# ice_tube_clock.net
KiCad netlist of a schematic drawn in EAGLE
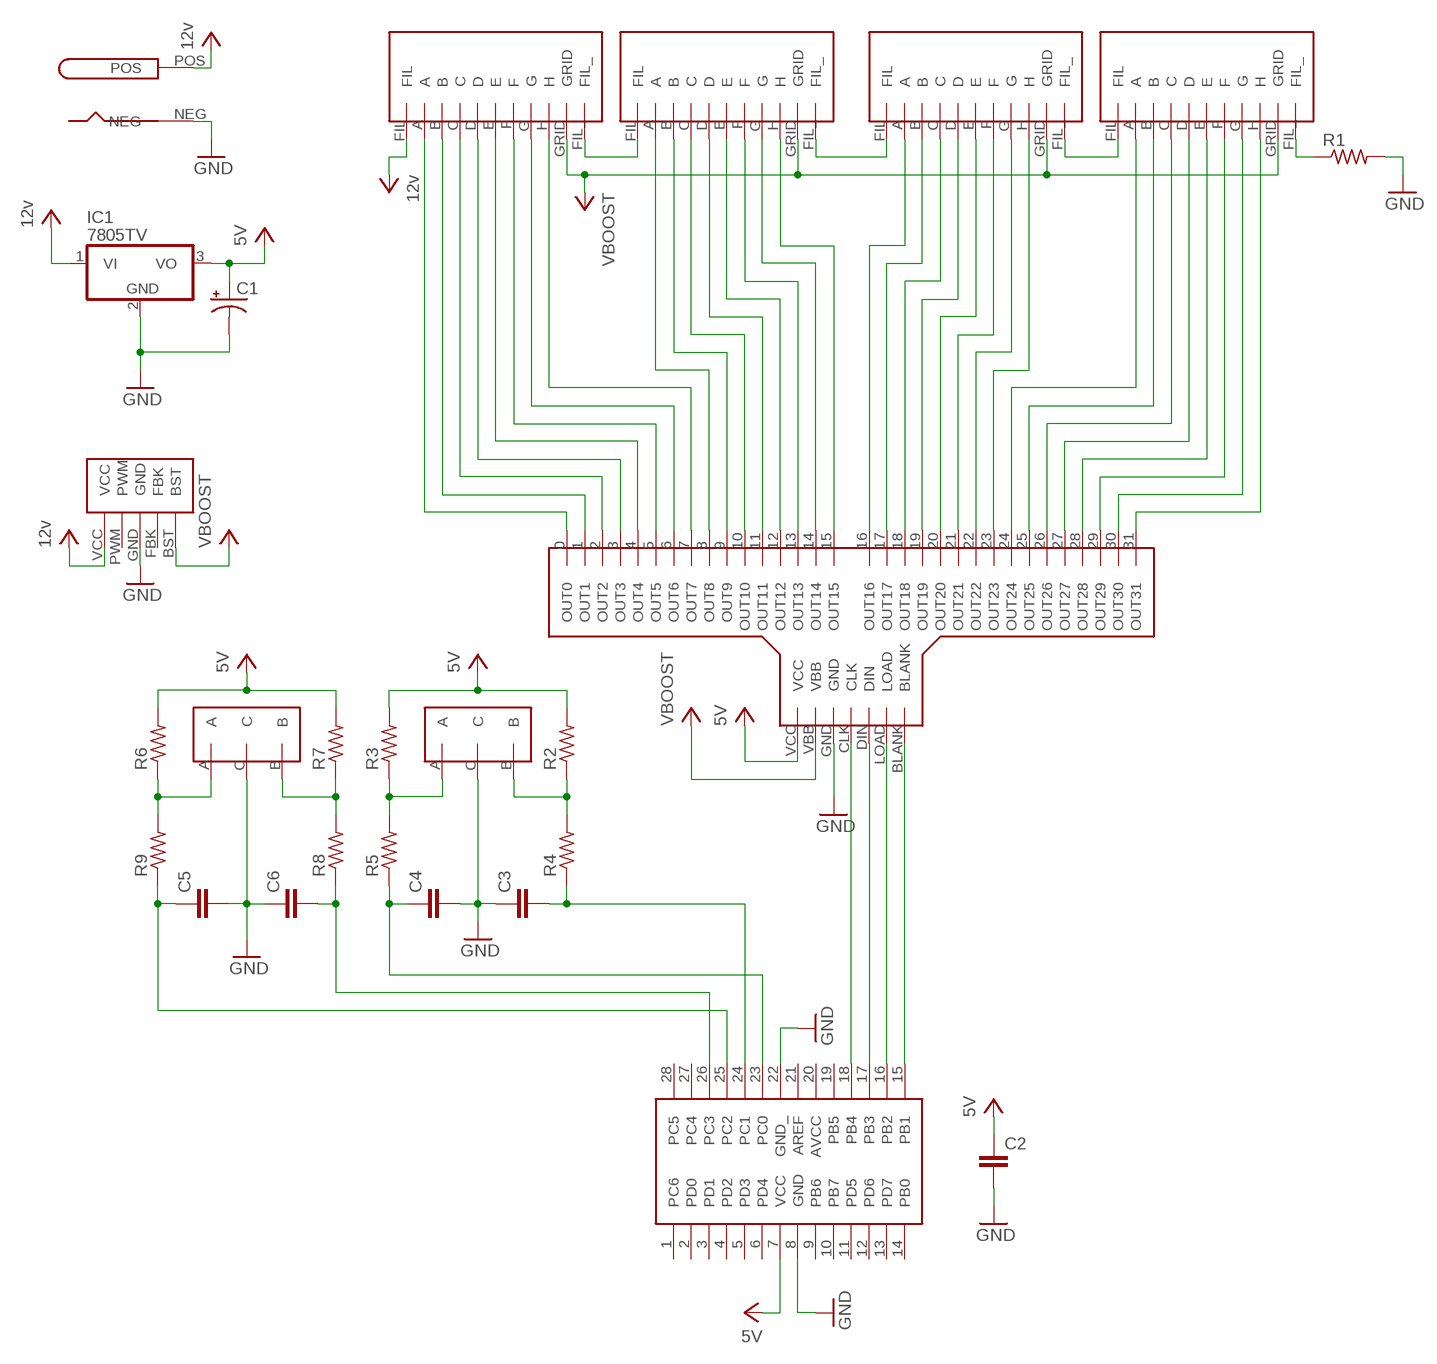
[diagram p0: schematic, sheet 1]

(export (version "E")
  (design (tool "Eeschema 10.0.6"))
  (components
    (comp (ref "C1")
      (value "CAP_POLPTH1")
      (footprint "eagle-import:CPOL-RADIAL-100UF-25V")
      (libsource (lib "eagle-import") (part "CAP_POLPTH1"))
    )
    (comp (ref "C2")
      (value "0.1UF-50V-20%(PTH)KIT-EZ")
      (footprint "eagle-import:CAP-PTH-SMALL-KIT")
      (libsource (lib "eagle-import") (part "0.1UF-50V-20%(PTH)KIT-EZ"))
    )
    (comp (ref "C3")
      (value "0.1UF-50V-20%(PTH)KIT-EZ")
      (footprint "eagle-import:CAP-PTH-SMALL-KIT")
      (libsource (lib "eagle-import") (part "0.1UF-50V-20%(PTH)KIT-EZ"))
    )
    (comp (ref "C4")
      (value "0.1UF-50V-20%(PTH)KIT-EZ")
      (footprint "eagle-import:CAP-PTH-SMALL-KIT")
      (libsource (lib "eagle-import") (part "0.1UF-50V-20%(PTH)KIT-EZ"))
    )
    (comp (ref "C5")
      (value "0.1UF-50V-20%(PTH)KIT-EZ")
      (footprint "eagle-import:CAP-PTH-SMALL-KIT")
      (libsource (lib "eagle-import") (part "0.1UF-50V-20%(PTH)KIT-EZ"))
    )
    (comp (ref "C6")
      (value "0.1UF-50V-20%(PTH)KIT-EZ")
      (footprint "eagle-import:CAP-PTH-SMALL-KIT")
      (libsource (lib "eagle-import") (part "0.1UF-50V-20%(PTH)KIT-EZ"))
    )
    (comp (ref "IC1")
      (value "7805TV")
      (footprint "eagle-import:TO220V")
      (libsource (lib "eagle-import") (part "78TV05"))
    )
    (comp (ref "R1")
      (value "R-US_0204/7")
      (footprint "eagle-import:0204_7")
      (libsource (lib "eagle-import") (part "R-US_0204/7"))
    )
    (comp (ref "R2")
      (value "R-US_0204/7")
      (footprint "eagle-import:0204_7")
      (libsource (lib "eagle-import") (part "R-US_0204/7"))
    )
    (comp (ref "R3")
      (value "R-US_0204/7")
      (footprint "eagle-import:0204_7")
      (libsource (lib "eagle-import") (part "R-US_0204/7"))
    )
    (comp (ref "R4")
      (value "R-US_0204/7")
      (footprint "eagle-import:0204_7")
      (libsource (lib "eagle-import") (part "R-US_0204/7"))
    )
    (comp (ref "R5")
      (value "R-US_0204/7")
      (footprint "eagle-import:0204_7")
      (libsource (lib "eagle-import") (part "R-US_0204/7"))
    )
    (comp (ref "R6")
      (value "R-US_0204/7")
      (footprint "eagle-import:0204_7")
      (libsource (lib "eagle-import") (part "R-US_0204/7"))
    )
    (comp (ref "R7")
      (value "R-US_0204/7")
      (footprint "eagle-import:0204_7")
      (libsource (lib "eagle-import") (part "R-US_0204/7"))
    )
    (comp (ref "R8")
      (value "R-US_0204/7")
      (footprint "eagle-import:0204_7")
      (libsource (lib "eagle-import") (part "R-US_0204/7"))
    )
    (comp (ref "R9")
      (value "R-US_0204/7")
      (footprint "eagle-import:0204_7")
      (libsource (lib "eagle-import") (part "R-US_0204/7"))
    )
    (comp (ref "U$1")
      (value "ATMEGA168-DIP28")
      (footprint "eagle-import:DIP28")
      (libsource (lib "eagle-import") (part "ATMEGA168-DIP28"))
    )
    (comp (ref "U$2")
      (value "IV11-BOOST-SUPPLY")
      (footprint "eagle-import:IV11-BOOST-SUPPLY")
      (libsource (lib "eagle-import") (part "IV11-BOOST-SUPPLY"))
    )
    (comp (ref "U$3")
      (value "IV-11-CARRIER")
      (footprint "eagle-import:IV-11-CARRIER")
      (libsource (lib "eagle-import") (part "IV-11-CARRIER"))
    )
    (comp (ref "U$4")
      (value "IV-11-CARRIER")
      (footprint "eagle-import:IV-11-CARRIER")
      (libsource (lib "eagle-import") (part "IV-11-CARRIER"))
    )
    (comp (ref "U$5")
      (value "IV-11-CARRIER")
      (footprint "eagle-import:IV-11-CARRIER")
      (libsource (lib "eagle-import") (part "IV-11-CARRIER"))
    )
    (comp (ref "U$6")
      (value "IV-11-CARRIER")
      (footprint "eagle-import:IV-11-CARRIER")
      (libsource (lib "eagle-import") (part "IV-11-CARRIER"))
    )
    (comp (ref "U$7")
      (value "PJ-037A")
      (footprint "eagle-import:PJ-037A")
      (libsource (lib "eagle-import") (part "PJ-037A"))
    )
    (comp (ref "U$8")
      (value "VFD-DRIVER-CARRIER")
      (footprint "eagle-import:VFD-DRIVER-CARRIER")
      (libsource (lib "eagle-import") (part "VFD-DRIVER-CARRIER"))
    )
    (comp (ref "U$9")
      (value "PEL12S")
      (footprint "eagle-import:PEL12S")
      (libsource (lib "eagle-import") (part "PEL12S"))
    )
    (comp (ref "U$10")
      (value "PEL12S")
      (footprint "eagle-import:PEL12S")
      (libsource (lib "eagle-import") (part "PEL12S"))
    )
  )
  (nets
    (net (code "1") (name "5V") (class "Default")
      (node (ref "C1") (pin "1") (pinfunction "+_1") (pintype "passive"))
      (node (ref "C2") (pin "1") (pinfunction "1_1") (pintype "passive"))
      (node (ref "IC1") (pin "3") (pinfunction "VO_3") (pintype "passive"))
      (node (ref "R2") (pin "2") (pinfunction "2_2") (pintype "passive"))
      (node (ref "R3") (pin "2") (pinfunction "2_2") (pintype "passive"))
      (node (ref "R6") (pin "2") (pinfunction "2_2") (pintype "passive"))
      (node (ref "R7") (pin "2") (pinfunction "2_2") (pintype "passive"))
      (node (ref "U$1") (pin "7") (pinfunction "VCC_7") (pintype "bidirectional"))
      (node (ref "U$8") (pin "VCC") (pinfunction "VCC_VCC") (pintype "bidirectional"))
    )
    (net (code "2") (name "12v") (class "Default")
      (node (ref "IC1") (pin "1") (pinfunction "VI_1") (pintype "input"))
      (node (ref "U$2") (pin "VCC") (pinfunction "VCC_VCC") (pintype "bidirectional"))
      (node (ref "U$3") (pin "FIL") (pinfunction "FIL_FIL") (pintype "bidirectional"))
      (node (ref "U$7") (pin "POS") (pinfunction "POS_POS") (pintype "bidirectional"))
    )
    (net (code "3") (name "GND") (class "Default")
      (node (ref "C1") (pin "2") (pinfunction "-_2") (pintype "passive"))
      (node (ref "C2") (pin "2") (pinfunction "2_2") (pintype "passive"))
      (node (ref "C3") (pin "1") (pinfunction "1_1") (pintype "passive"))
      (node (ref "C4") (pin "2") (pinfunction "2_2") (pintype "passive"))
      (node (ref "C5") (pin "2") (pinfunction "2_2") (pintype "passive"))
      (node (ref "C6") (pin "1") (pinfunction "1_1") (pintype "passive"))
      (node (ref "IC1") (pin "2") (pinfunction "GND_2") (pintype "passive"))
      (node (ref "R1") (pin "2") (pinfunction "2_2") (pintype "passive"))
      (node (ref "U$1") (pin "22") (pinfunction "GND__22") (pintype "bidirectional"))
      (node (ref "U$1") (pin "8") (pinfunction "GND_8") (pintype "bidirectional"))
      (node (ref "U$10") (pin "C") (pinfunction "C_C") (pintype "bidirectional"))
      (node (ref "U$2") (pin "GND") (pinfunction "GND_GND") (pintype "bidirectional"))
      (node (ref "U$7") (pin "NEG") (pinfunction "NEG_NEG") (pintype "bidirectional"))
      (node (ref "U$8") (pin "GND") (pinfunction "GND_GND") (pintype "bidirectional"))
      (node (ref "U$9") (pin "C") (pinfunction "C_C") (pintype "bidirectional"))
    )
    (net (code "4") (name "Net-(R1-Pad1)") (class "Default")
      (node (ref "R1") (pin "1") (pinfunction "1_1") (pintype "passive"))
      (node (ref "U$6") (pin "FIL_") (pinfunction "FIL__FIL_") (pintype "bidirectional"))
    )
    (net (code "5") (name "Net-(R2-Pad1)") (class "Default")
      (node (ref "R2") (pin "1") (pinfunction "1_1") (pintype "passive"))
      (node (ref "R4") (pin "2") (pinfunction "2_2") (pintype "passive"))
      (node (ref "U$10") (pin "B") (pinfunction "B_B") (pintype "bidirectional"))
    )
    (net (code "6") (name "Net-(R3-Pad1)") (class "Default")
      (node (ref "R3") (pin "1") (pinfunction "1_1") (pintype "passive"))
      (node (ref "R5") (pin "2") (pinfunction "2_2") (pintype "passive"))
      (node (ref "U$10") (pin "A") (pinfunction "A_A") (pintype "bidirectional"))
    )
    (net (code "7") (name "Net-(R6-Pad1)") (class "Default")
      (node (ref "R6") (pin "1") (pinfunction "1_1") (pintype "passive"))
      (node (ref "R9") (pin "2") (pinfunction "2_2") (pintype "passive"))
      (node (ref "U$9") (pin "A") (pinfunction "A_A") (pintype "bidirectional"))
    )
    (net (code "8") (name "Net-(R7-Pad1)") (class "Default")
      (node (ref "R7") (pin "1") (pinfunction "1_1") (pintype "passive"))
      (node (ref "R8") (pin "2") (pinfunction "2_2") (pintype "passive"))
      (node (ref "U$9") (pin "B") (pinfunction "B_B") (pintype "bidirectional"))
    )
    (net (code "9") (name "Net-(U$1-PB1)") (class "Default")
      (node (ref "U$1") (pin "15") (pinfunction "PB1_15") (pintype "bidirectional"))
      (node (ref "U$8") (pin "BLANK") (pinfunction "BLANK_BLANK") (pintype "bidirectional"))
    )
    (net (code "10") (name "Net-(U$1-PB2)") (class "Default")
      (node (ref "U$1") (pin "16") (pinfunction "PB2_16") (pintype "bidirectional"))
      (node (ref "U$8") (pin "LOAD") (pinfunction "LOAD_LOAD") (pintype "bidirectional"))
    )
    (net (code "11") (name "Net-(U$1-PB3)") (class "Default")
      (node (ref "U$1") (pin "17") (pinfunction "PB3_17") (pintype "bidirectional"))
      (node (ref "U$8") (pin "DIN") (pinfunction "DIN_DIN") (pintype "bidirectional"))
    )
    (net (code "12") (name "Net-(U$1-PB4)") (class "Default")
      (node (ref "U$1") (pin "18") (pinfunction "PB4_18") (pintype "bidirectional"))
      (node (ref "U$8") (pin "CLK") (pinfunction "CLK_CLK") (pintype "bidirectional"))
    )
    (net (code "13") (name "Net-(U$1-PC0)") (class "Default")
      (node (ref "C4") (pin "1") (pinfunction "1_1") (pintype "passive"))
      (node (ref "R5") (pin "1") (pinfunction "1_1") (pintype "passive"))
      (node (ref "U$1") (pin "23") (pinfunction "PC0_23") (pintype "bidirectional"))
    )
    (net (code "14") (name "Net-(U$1-PC1)") (class "Default")
      (node (ref "C3") (pin "2") (pinfunction "2_2") (pintype "passive"))
      (node (ref "R4") (pin "1") (pinfunction "1_1") (pintype "passive"))
      (node (ref "U$1") (pin "24") (pinfunction "PC1_24") (pintype "bidirectional"))
    )
    (net (code "15") (name "Net-(U$1-PC2)") (class "Default")
      (node (ref "C5") (pin "1") (pinfunction "1_1") (pintype "passive"))
      (node (ref "R9") (pin "1") (pinfunction "1_1") (pintype "passive"))
      (node (ref "U$1") (pin "25") (pinfunction "PC2_25") (pintype "bidirectional"))
    )
    (net (code "16") (name "Net-(U$1-PC3)") (class "Default")
      (node (ref "C6") (pin "2") (pinfunction "2_2") (pintype "passive"))
      (node (ref "R8") (pin "1") (pinfunction "1_1") (pintype "passive"))
      (node (ref "U$1") (pin "26") (pinfunction "PC3_26") (pintype "bidirectional"))
    )
    (net (code "17") (name "Net-(U$3-PadFIL_)") (class "Default")
      (node (ref "U$3") (pin "FIL_") (pinfunction "FIL__FIL_") (pintype "bidirectional"))
      (node (ref "U$4") (pin "FIL") (pinfunction "FIL_FIL") (pintype "bidirectional"))
    )
    (net (code "18") (name "Net-(U$4-PadFIL_)") (class "Default")
      (node (ref "U$4") (pin "FIL_") (pinfunction "FIL__FIL_") (pintype "bidirectional"))
      (node (ref "U$5") (pin "FIL") (pinfunction "FIL_FIL") (pintype "bidirectional"))
    )
    (net (code "19") (name "Net-(U$5-PadFIL_)") (class "Default")
      (node (ref "U$5") (pin "FIL_") (pinfunction "FIL__FIL_") (pintype "bidirectional"))
      (node (ref "U$6") (pin "FIL") (pinfunction "FIL_FIL") (pintype "bidirectional"))
    )
    (net (code "20") (name "Net-(U$8-OUT0)") (class "Default")
      (node (ref "U$3") (pin "A") (pinfunction "A_A") (pintype "bidirectional"))
      (node (ref "U$8") (pin "0") (pinfunction "OUT0_0") (pintype "bidirectional"))
    )
    (net (code "21") (name "Net-(U$8-OUT1)") (class "Default")
      (node (ref "U$3") (pin "B") (pinfunction "B_B") (pintype "bidirectional"))
      (node (ref "U$8") (pin "1") (pinfunction "OUT1_1") (pintype "bidirectional"))
    )
    (net (code "22") (name "Net-(U$8-OUT2)") (class "Default")
      (node (ref "U$3") (pin "C") (pinfunction "C_C") (pintype "bidirectional"))
      (node (ref "U$8") (pin "2") (pinfunction "OUT2_2") (pintype "bidirectional"))
    )
    (net (code "23") (name "Net-(U$8-OUT3)") (class "Default")
      (node (ref "U$3") (pin "D") (pinfunction "D_D") (pintype "bidirectional"))
      (node (ref "U$8") (pin "3") (pinfunction "OUT3_3") (pintype "bidirectional"))
    )
    (net (code "24") (name "Net-(U$8-OUT4)") (class "Default")
      (node (ref "U$3") (pin "E") (pinfunction "E_E") (pintype "bidirectional"))
      (node (ref "U$8") (pin "4") (pinfunction "OUT4_4") (pintype "bidirectional"))
    )
    (net (code "25") (name "Net-(U$8-OUT5)") (class "Default")
      (node (ref "U$3") (pin "F") (pinfunction "F_F") (pintype "bidirectional"))
      (node (ref "U$8") (pin "5") (pinfunction "OUT5_5") (pintype "bidirectional"))
    )
    (net (code "26") (name "Net-(U$8-OUT6)") (class "Default")
      (node (ref "U$3") (pin "G") (pinfunction "G_G") (pintype "bidirectional"))
      (node (ref "U$8") (pin "6") (pinfunction "OUT6_6") (pintype "bidirectional"))
    )
    (net (code "27") (name "Net-(U$8-OUT7)") (class "Default")
      (node (ref "U$3") (pin "H") (pinfunction "H_H") (pintype "bidirectional"))
      (node (ref "U$8") (pin "7") (pinfunction "OUT7_7") (pintype "bidirectional"))
    )
    (net (code "28") (name "Net-(U$8-OUT8)") (class "Default")
      (node (ref "U$4") (pin "A") (pinfunction "A_A") (pintype "bidirectional"))
      (node (ref "U$8") (pin "8") (pinfunction "OUT8_8") (pintype "bidirectional"))
    )
    (net (code "29") (name "Net-(U$8-OUT9)") (class "Default")
      (node (ref "U$4") (pin "B") (pinfunction "B_B") (pintype "bidirectional"))
      (node (ref "U$8") (pin "9") (pinfunction "OUT9_9") (pintype "bidirectional"))
    )
    (net (code "30") (name "Net-(U$8-OUT10)") (class "Default")
      (node (ref "U$4") (pin "C") (pinfunction "C_C") (pintype "bidirectional"))
      (node (ref "U$8") (pin "10") (pinfunction "OUT10_10") (pintype "bidirectional"))
    )
    (net (code "31") (name "Net-(U$8-OUT11)") (class "Default")
      (node (ref "U$4") (pin "D") (pinfunction "D_D") (pintype "bidirectional"))
      (node (ref "U$8") (pin "11") (pinfunction "OUT11_11") (pintype "bidirectional"))
    )
    (net (code "32") (name "Net-(U$8-OUT12)") (class "Default")
      (node (ref "U$4") (pin "E") (pinfunction "E_E") (pintype "bidirectional"))
      (node (ref "U$8") (pin "12") (pinfunction "OUT12_12") (pintype "bidirectional"))
    )
    (net (code "33") (name "Net-(U$8-OUT13)") (class "Default")
      (node (ref "U$4") (pin "F") (pinfunction "F_F") (pintype "bidirectional"))
      (node (ref "U$8") (pin "13") (pinfunction "OUT13_13") (pintype "bidirectional"))
    )
    (net (code "34") (name "Net-(U$8-OUT14)") (class "Default")
      (node (ref "U$4") (pin "G") (pinfunction "G_G") (pintype "bidirectional"))
      (node (ref "U$8") (pin "14") (pinfunction "OUT14_14") (pintype "bidirectional"))
    )
    (net (code "35") (name "Net-(U$8-OUT15)") (class "Default")
      (node (ref "U$4") (pin "H") (pinfunction "H_H") (pintype "bidirectional"))
      (node (ref "U$8") (pin "15") (pinfunction "OUT15_15") (pintype "bidirectional"))
    )
    (net (code "36") (name "Net-(U$8-OUT16)") (class "Default")
      (node (ref "U$5") (pin "A") (pinfunction "A_A") (pintype "bidirectional"))
      (node (ref "U$8") (pin "16") (pinfunction "OUT16_16") (pintype "bidirectional"))
    )
    (net (code "37") (name "Net-(U$8-OUT17)") (class "Default")
      (node (ref "U$5") (pin "B") (pinfunction "B_B") (pintype "bidirectional"))
      (node (ref "U$8") (pin "17") (pinfunction "OUT17_17") (pintype "bidirectional"))
    )
    (net (code "38") (name "Net-(U$8-OUT18)") (class "Default")
      (node (ref "U$5") (pin "C") (pinfunction "C_C") (pintype "bidirectional"))
      (node (ref "U$8") (pin "18") (pinfunction "OUT18_18") (pintype "bidirectional"))
    )
    (net (code "39") (name "Net-(U$8-OUT19)") (class "Default")
      (node (ref "U$5") (pin "D") (pinfunction "D_D") (pintype "bidirectional"))
      (node (ref "U$8") (pin "19") (pinfunction "OUT19_19") (pintype "bidirectional"))
    )
    (net (code "40") (name "Net-(U$8-OUT20)") (class "Default")
      (node (ref "U$5") (pin "E") (pinfunction "E_E") (pintype "bidirectional"))
      (node (ref "U$8") (pin "20") (pinfunction "OUT20_20") (pintype "bidirectional"))
    )
    (net (code "41") (name "Net-(U$8-OUT21)") (class "Default")
      (node (ref "U$5") (pin "F") (pinfunction "F_F") (pintype "bidirectional"))
      (node (ref "U$8") (pin "21") (pinfunction "OUT21_21") (pintype "bidirectional"))
    )
    (net (code "42") (name "Net-(U$8-OUT22)") (class "Default")
      (node (ref "U$5") (pin "G") (pinfunction "G_G") (pintype "bidirectional"))
      (node (ref "U$8") (pin "22") (pinfunction "OUT22_22") (pintype "bidirectional"))
    )
    (net (code "43") (name "Net-(U$8-OUT23)") (class "Default")
      (node (ref "U$5") (pin "H") (pinfunction "H_H") (pintype "bidirectional"))
      (node (ref "U$8") (pin "23") (pinfunction "OUT23_23") (pintype "bidirectional"))
    )
    (net (code "44") (name "Net-(U$8-OUT24)") (class "Default")
      (node (ref "U$6") (pin "A") (pinfunction "A_A") (pintype "bidirectional"))
      (node (ref "U$8") (pin "24") (pinfunction "OUT24_24") (pintype "bidirectional"))
    )
    (net (code "45") (name "Net-(U$8-OUT25)") (class "Default")
      (node (ref "U$6") (pin "B") (pinfunction "B_B") (pintype "bidirectional"))
      (node (ref "U$8") (pin "25") (pinfunction "OUT25_25") (pintype "bidirectional"))
    )
    (net (code "46") (name "Net-(U$8-OUT26)") (class "Default")
      (node (ref "U$6") (pin "C") (pinfunction "C_C") (pintype "bidirectional"))
      (node (ref "U$8") (pin "26") (pinfunction "OUT26_26") (pintype "bidirectional"))
    )
    (net (code "47") (name "Net-(U$8-OUT27)") (class "Default")
      (node (ref "U$6") (pin "D") (pinfunction "D_D") (pintype "bidirectional"))
      (node (ref "U$8") (pin "27") (pinfunction "OUT27_27") (pintype "bidirectional"))
    )
    (net (code "48") (name "Net-(U$8-OUT28)") (class "Default")
      (node (ref "U$6") (pin "E") (pinfunction "E_E") (pintype "bidirectional"))
      (node (ref "U$8") (pin "28") (pinfunction "OUT28_28") (pintype "bidirectional"))
    )
    (net (code "49") (name "Net-(U$8-OUT29)") (class "Default")
      (node (ref "U$6") (pin "F") (pinfunction "F_F") (pintype "bidirectional"))
      (node (ref "U$8") (pin "29") (pinfunction "OUT29_29") (pintype "bidirectional"))
    )
    (net (code "50") (name "Net-(U$8-OUT30)") (class "Default")
      (node (ref "U$6") (pin "G") (pinfunction "G_G") (pintype "bidirectional"))
      (node (ref "U$8") (pin "30") (pinfunction "OUT30_30") (pintype "bidirectional"))
    )
    (net (code "51") (name "Net-(U$8-OUT31)") (class "Default")
      (node (ref "U$6") (pin "H") (pinfunction "H_H") (pintype "bidirectional"))
      (node (ref "U$8") (pin "31") (pinfunction "OUT31_31") (pintype "bidirectional"))
    )
    (net (code "52") (name "VBOOST") (class "Default")
      (node (ref "U$2") (pin "BST") (pinfunction "BST_BST") (pintype "bidirectional"))
      (node (ref "U$3") (pin "GRID") (pinfunction "GRID_GRID") (pintype "bidirectional"))
      (node (ref "U$4") (pin "GRID") (pinfunction "GRID_GRID") (pintype "bidirectional"))
      (node (ref "U$5") (pin "GRID") (pinfunction "GRID_GRID") (pintype "bidirectional"))
      (node (ref "U$6") (pin "GRID") (pinfunction "GRID_GRID") (pintype "bidirectional"))
      (node (ref "U$8") (pin "VBB") (pinfunction "VBB_VBB") (pintype "bidirectional"))
    )
    (net (code "53") (name "unconnected-(U$1-AREF-Pad21)") (class "Default")
      (node (ref "U$1") (pin "21") (pinfunction "AREF_21") (pintype "bidirectional"))
    )
    (net (code "54") (name "unconnected-(U$1-AVCC-Pad20)") (class "Default")
      (node (ref "U$1") (pin "20") (pinfunction "AVCC_20") (pintype "bidirectional"))
    )
    (net (code "55") (name "unconnected-(U$1-PB0-Pad14)") (class "Default")
      (node (ref "U$1") (pin "14") (pinfunction "PB0_14") (pintype "bidirectional"))
    )
    (net (code "56") (name "unconnected-(U$1-PB5-Pad19)") (class "Default")
      (node (ref "U$1") (pin "19") (pinfunction "PB5_19") (pintype "bidirectional"))
    )
    (net (code "57") (name "unconnected-(U$1-PB6-Pad9)") (class "Default")
      (node (ref "U$1") (pin "9") (pinfunction "PB6_9") (pintype "bidirectional"))
    )
    (net (code "58") (name "unconnected-(U$1-PB7-Pad10)") (class "Default")
      (node (ref "U$1") (pin "10") (pinfunction "PB7_10") (pintype "bidirectional"))
    )
    (net (code "59") (name "unconnected-(U$1-PC4-Pad27)") (class "Default")
      (node (ref "U$1") (pin "27") (pinfunction "PC4_27") (pintype "bidirectional"))
    )
    (net (code "60") (name "unconnected-(U$1-PC5-Pad28)") (class "Default")
      (node (ref "U$1") (pin "28") (pinfunction "PC5_28") (pintype "bidirectional"))
    )
    (net (code "61") (name "unconnected-(U$1-PC6-Pad1)") (class "Default")
      (node (ref "U$1") (pin "1") (pinfunction "PC6_1") (pintype "bidirectional"))
    )
    (net (code "62") (name "unconnected-(U$1-PD0-Pad2)") (class "Default")
      (node (ref "U$1") (pin "2") (pinfunction "PD0_2") (pintype "bidirectional"))
    )
    (net (code "63") (name "unconnected-(U$1-PD1-Pad3)") (class "Default")
      (node (ref "U$1") (pin "3") (pinfunction "PD1_3") (pintype "bidirectional"))
    )
    (net (code "64") (name "unconnected-(U$1-PD2-Pad4)") (class "Default")
      (node (ref "U$1") (pin "4") (pinfunction "PD2_4") (pintype "bidirectional"))
    )
    (net (code "65") (name "unconnected-(U$1-PD3-Pad5)") (class "Default")
      (node (ref "U$1") (pin "5") (pinfunction "PD3_5") (pintype "bidirectional"))
    )
    (net (code "66") (name "unconnected-(U$1-PD4-Pad6)") (class "Default")
      (node (ref "U$1") (pin "6") (pinfunction "PD4_6") (pintype "bidirectional"))
    )
    (net (code "67") (name "unconnected-(U$1-PD5-Pad11)") (class "Default")
      (node (ref "U$1") (pin "11") (pinfunction "PD5_11") (pintype "bidirectional"))
    )
    (net (code "68") (name "unconnected-(U$1-PD6-Pad12)") (class "Default")
      (node (ref "U$1") (pin "12") (pinfunction "PD6_12") (pintype "bidirectional"))
    )
    (net (code "69") (name "unconnected-(U$1-PD7-Pad13)") (class "Default")
      (node (ref "U$1") (pin "13") (pinfunction "PD7_13") (pintype "bidirectional"))
    )
    (net (code "70") (name "unconnected-(U$2-PadFBK)") (class "Default")
      (node (ref "U$2") (pin "FBK") (pinfunction "FBK_FBK") (pintype "bidirectional"))
    )
    (net (code "71") (name "unconnected-(U$2-PadPWM)") (class "Default")
      (node (ref "U$2") (pin "PWM") (pinfunction "PWM_PWM") (pintype "bidirectional"))
    )
  )
)
